# 02-Power.net
KiCad netlist of a schematic drawn in Altium Designer
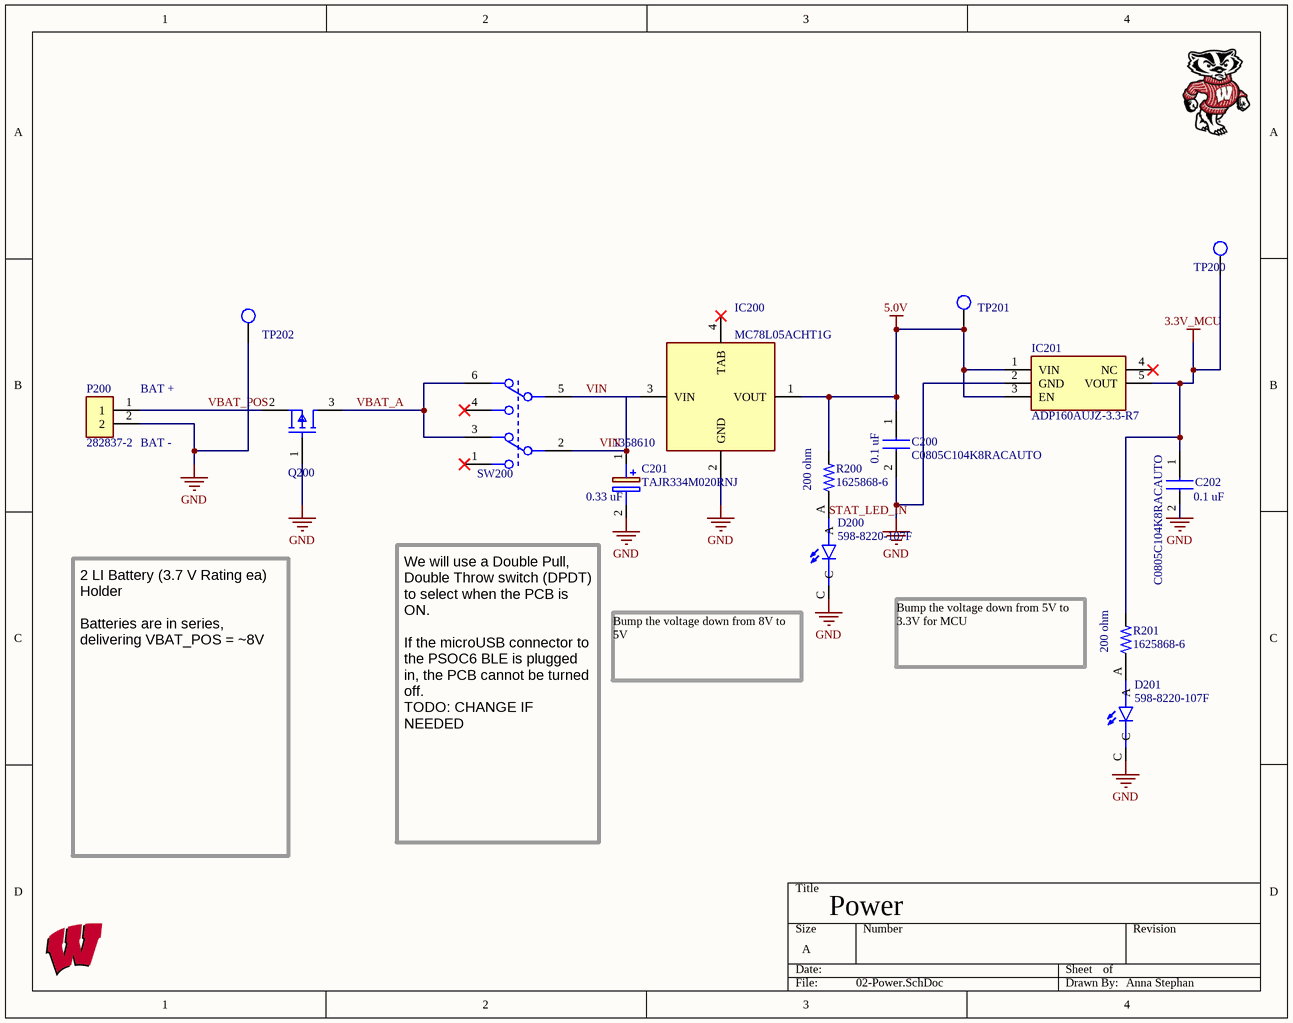
[diagram p0: 02-Power.SchDoc]

(export (version "E")
  (design (tool "Eeschema 10.0.6"))
  (components
    (comp (ref "C200")
      (value "C0805C104K8RACAUTO")
      (footprint "CAPC2012X88N")
      (description "Capacitor")
      (fields (field (name "MOUSER2 PART NUMBER") "80-C0805C104K8RAUTO"))
      (libsource (lib "453lib") (part "C0805C104K8RACAUTO"))
    )
    (comp (ref "C201")
      (value "TAJR334M020RNJ")
      (footprint "CAPM3216X18N")
      (description "Capacitor Polarised")
      (fields
        (field (name "MOUSER2 PART NUMBER") "581-TAJR334M020RNJ")
        (field (name "SUPPLIER PART NUMBER 1") "1358610")
      )
      (libsource (lib "453lib") (part "TAJR334M020RNJ"))
    )
    (comp (ref "C202")
      (value "C0805C104K8RACAUTO")
      (footprint "CAPC2012X88N")
      (description "Capacitor")
      (fields (field (name "MOUSER2 PART NUMBER") "80-C0805C104K8RAUTO"))
      (libsource (lib "453lib") (part "C0805C104K8RACAUTO"))
    )
    (comp (ref "D200")
      (value "598-8220-107F")
      (footprint "LEDSC160X320X90-2N")
      (description "Red 625nm LED Indication - Discrete 2V 1206 _3216 Metric_")
      (fields (field (name "MF") "Dialight"))
      (libsource (lib "453lib") (part "598-8220-107F"))
    )
    (comp (ref "D201")
      (value "598-8220-107F")
      (footprint "LEDSC160X320X90-2N")
      (description "Red 625nm LED Indication - Discrete 2V 1206 _3216 Metric_")
      (fields (field (name "MF") "Dialight"))
      (libsource (lib "453lib") (part "598-8220-107F"))
    )
    (comp (ref "IC200")
      (value "MC78L05ACHT1G")
      (footprint "SOT89-150P415X160-3N")
      (description "Integrated Circuit")
      (fields (field (name "MOUSER2 PART NUMBER") "863-MC78L05ACHT1G"))
      (libsource (lib "453lib") (part "MC78L05ACHT1G"))
    )
    (comp (ref "IC201")
      (value "ADP160AUJZ-3.3-R7")
      (footprint "TSOT23127P600-8N")
      (description "Integrated Circuit")
      (fields
        (field (name "MOUSER2 PART NUMBER") "584-ADP160AUJZ-3.3R7")
        (field (name "MANUFACTURER_PART_NUMBER") "ADP160AUJZ-3.0-R7")
      )
      (libsource (lib "453lib") (part "ADP160AUJZ-3.0-R7"))
    )
    (comp (ref "P200")
      (value "282837-2")
      (footprint "TE_282837-2:TE_282837-2")
      (description "Connector Terminal Blocks Receptacle 2 Position 5.08mm Solder Straight Thru-Hole 13.5A/Contact")
      (fields
        (field (name "MF") "TE Connectivity")
        (field (name "MANUFACTURER") "TE Connectivity AMP Connectors")
      )
      (libsource (lib "282837-2") (part "282837-2"))
    )
    (comp (ref "Q200")
      (value "SSM3J328R,LF")
      (footprint "SOT-23_M")
      (description "MOSFET P-CH 20V 6A SOT23F")
      (libsource (lib "ECE453-S22") (part "SSM3J328R,LF"))
    )
    (comp (ref "R200")
      (value "1625868-6")
      (footprint "453lib:RESC2012X65N")
      (description "Resistor 0805 200R 0.1% 25ppm (reel)")
      (libsource (lib "453lib") (part "1625868-6"))
    )
    (comp (ref "R201")
      (value "1625868-6")
      (footprint "453lib:RESC2012X65N")
      (description "Resistor 0805 200R 0.1% 25ppm (reel)")
      (libsource (lib "453lib") (part "1625868-6"))
    )
    (comp (ref "SW200")
      (value "MHS22204")
      (footprint "C&K_Components_0_MFG")
      (description "C & K COMPONENTS - JS202011SCQN - SWITCH, DPDT, 0.6A, 6VDC, SMD")
      (libsource (lib "ECE453-S22") (part "JS202011SCQN"))
    )
    (comp (ref "TP200")
      (value "TP_1206")
      (footprint "TP-SMC-1206")
      (description "Test Point SMD 1206")
      (fields
        (field (name "MANUFACTURER") "TE Connectivity (Tyco Electronics)")
        (field (name "MANUFACTURER PART NUMBER") "1625854-1")
      )
      (libsource (lib "ECE453-S22") (part "TP_1206"))
    )
    (comp (ref "TP201")
      (value "TP_1206")
      (footprint "TP-SMC-1206")
      (description "Test Point SMD 1206")
      (fields
        (field (name "MANUFACTURER") "TE Connectivity (Tyco Electronics)")
        (field (name "MANUFACTURER PART NUMBER") "1625854-1")
      )
      (libsource (lib "ECE453-S22") (part "TP_1206"))
    )
    (comp (ref "TP202")
      (value "TP_1206")
      (footprint "TP-SMC-1206")
      (description "Test Point SMD 1206")
      (fields
        (field (name "MANUFACTURER") "TE Connectivity (Tyco Electronics)")
        (field (name "MANUFACTURER PART NUMBER") "1625854-1")
      )
      (libsource (lib "ECE453-S22") (part "TP_1206"))
    )
  )
  (nets
    (net (code "2") (name "/VBAT_A") (class "Default")
      (node (ref "Q200") (pin "3") (pinfunction "Drain_3") (pintype "passive"))
      (node (ref "SW200") (pin "3") (pinfunction "3_3") (pintype "passive"))
      (node (ref "SW200") (pin "6") (pinfunction "6_6") (pintype "passive"))
    )
    (net (code "3") (name "/VBAT_POS") (class "Default")
      (node (ref "P200") (pin "1") (pinfunction "1_1") (pintype "passive"))
      (node (ref "Q200") (pin "2") (pinfunction "Source_2") (pintype "passive"))
    )
    (net (code "4") (name "/VIN") (class "Default")
      (node (ref "C201") (pin "1") (pinfunction "+_1") (pintype "passive"))
      (node (ref "IC200") (pin "3") (pinfunction "VIN_3") (pintype "passive"))
      (node (ref "SW200") (pin "2") (pinfunction "2_2") (pintype "passive"))
      (node (ref "SW200") (pin "5") (pinfunction "5_5") (pintype "passive"))
    )
    (net (code "5") (name "3.3V_MCU") (class "Default")
      (node (ref "C202") (pin "1") (pinfunction "1_1") (pintype "passive"))
      (node (ref "IC201") (pin "5") (pinfunction "VOUT_5") (pintype "passive"))
      (node (ref "R201") (pin "2") (pinfunction "2_2") (pintype "passive"))
      (node (ref "TP200") (pin "1") (pintype "passive"))
    )
    (net (code "6") (name "5.0V") (class "Default")
      (node (ref "C200") (pin "1") (pinfunction "1_1") (pintype "passive"))
      (node (ref "IC200") (pin "1") (pinfunction "VOUT_1") (pintype "passive"))
      (node (ref "IC201") (pin "1") (pinfunction "VIN_1") (pintype "passive"))
      (node (ref "IC201") (pin "3") (pinfunction "EN_3") (pintype "passive"))
      (node (ref "R200") (pin "2") (pinfunction "2_2") (pintype "passive"))
      (node (ref "TP201") (pin "1") (pintype "passive"))
    )
    (net (code "7") (name "GND") (class "Default")
      (node (ref "C200") (pin "2") (pinfunction "2_2") (pintype "passive"))
      (node (ref "C201") (pin "2") (pinfunction "-_2") (pintype "passive"))
      (node (ref "C202") (pin "2") (pinfunction "2_2") (pintype "passive"))
      (node (ref "D200") (pin "C") (pinfunction "C_C") (pintype "passive"))
      (node (ref "D201") (pin "C") (pinfunction "C_C") (pintype "passive"))
      (node (ref "IC200") (pin "2") (pinfunction "GND_2") (pintype "passive"))
      (node (ref "IC201") (pin "2") (pinfunction "GND_2") (pintype "passive"))
      (node (ref "P200") (pin "2") (pinfunction "2_2") (pintype "passive"))
      (node (ref "Q200") (pin "1") (pinfunction "Gate_1") (pintype "passive"))
      (node (ref "TP202") (pin "1") (pintype "passive"))
    )
    (net (code "8") (name "Net-(D200-PadA)") (class "Default")
      (node (ref "D200") (pin "A") (pinfunction "A_A") (pintype "passive"))
      (node (ref "R200") (pin "1") (pinfunction "1_1") (pintype "passive"))
    )
    (net (code "9") (name "Net-(D201-PadA)") (class "Default")
      (node (ref "D201") (pin "A") (pinfunction "A_A") (pintype "passive"))
      (node (ref "R201") (pin "1") (pinfunction "1_1") (pintype "passive"))
    )
    (net (code "10") (name "unconnected-(IC200-TAB-Pad4)") (class "Default")
      (node (ref "IC200") (pin "4") (pinfunction "TAB_4") (pintype "passive+no_connect"))
    )
    (net (code "11") (name "unconnected-(IC201-NC-Pad4)") (class "Default")
      (node (ref "IC201") (pin "4") (pinfunction "NC_4") (pintype "passive+no_connect"))
    )
    (net (code "12") (name "unconnected-(SW200-Pad1)") (class "Default")
      (node (ref "SW200") (pin "1") (pinfunction "1_1") (pintype "passive+no_connect"))
    )
    (net (code "13") (name "unconnected-(SW200-Pad4)") (class "Default")
      (node (ref "SW200") (pin "4") (pinfunction "4_4") (pintype "passive+no_connect"))
    )
  )
)
